# A-Main.net
KiCad netlist of a schematic drawn in Altium Designer
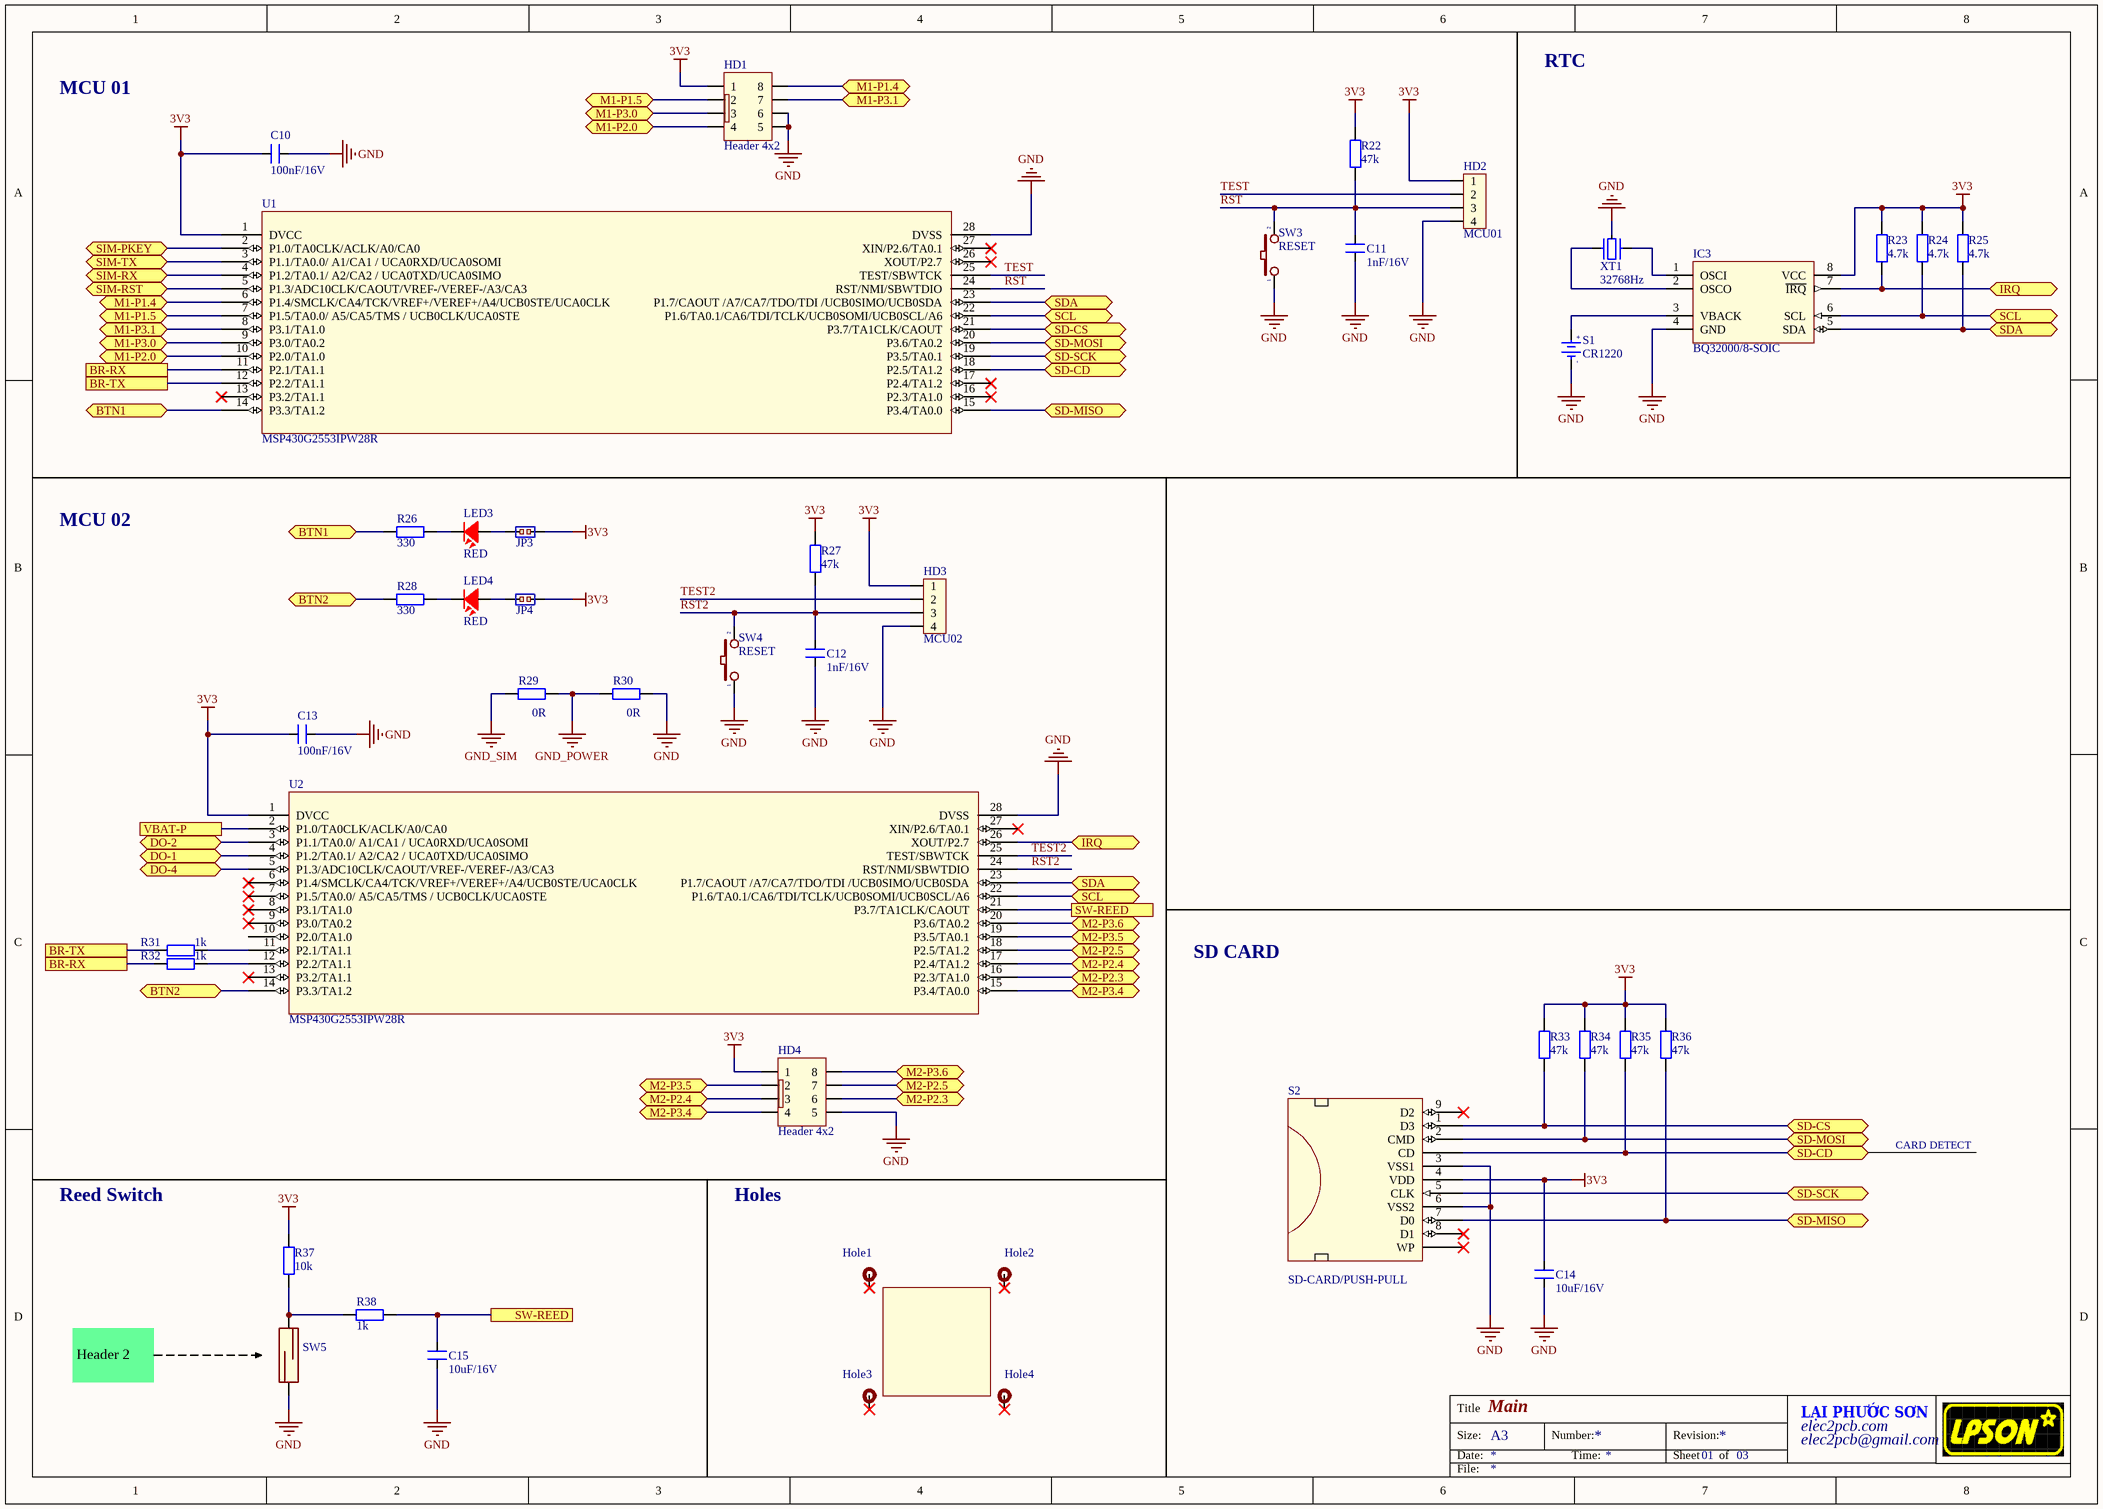
[diagram p0: A-Main.SchDoc]

(export (version "E")
  (design (tool "Eeschema 10.0.6"))
  (components
    (comp (ref "C10")
      (value "100nF/16V")
      (footprint "C0805-2012")
      (description "CAP CER 0.1UF 16V X7R 0805")
      (fields
        (field (name "MANUFACTURER") "Kemet")
        (field (name "MANUFACTURER PART NUMBER") "C0805C104K4RACTU")
      )
      (libsource (lib "Tran Tuan") (part "CAP-CER/100nF/16V/X7R/0805"))
    )
    (comp (ref "C11")
      (value "1nF/16V")
      (footprint "C0603-1608")
      (description "CAP CER 1000PF 16V X7R 0603")
      (fields
        (field (name "MANUFACTURER") "AVX Corporation")
        (field (name "MANUFACTURER PART NUMBER") "0603YC102KAT2A")
      )
      (libsource (lib "Tran Tuan") (part "CAP-CER/1nF/16V/X7R/0603"))
    )
    (comp (ref "C12")
      (value "1nF/16V")
      (footprint "C0603-1608")
      (description "CAP CER 1000PF 16V X7R 0603")
      (fields
        (field (name "MANUFACTURER") "AVX Corporation")
        (field (name "MANUFACTURER PART NUMBER") "0603YC102KAT2A")
      )
      (libsource (lib "Tran Tuan") (part "CAP-CER/1nF/16V/X7R/0603"))
    )
    (comp (ref "C13")
      (value "100nF/16V")
      (footprint "C0805-2012")
      (description "CAP CER 0.1UF 16V X7R 0805")
      (fields
        (field (name "MANUFACTURER") "Kemet")
        (field (name "MANUFACTURER PART NUMBER") "C0805C104K4RACTU")
      )
      (libsource (lib "Tran Tuan") (part "CAP-CER/100nF/16V/X7R/0805"))
    )
    (comp (ref "C14")
      (value "10uF/16V")
      (footprint "C0805-2012")
      (description "CAP CER 10UF 16V X5R 0805")
      (fields
        (field (name "MANUFACTURER") "Murata Electronics North America")
        (field (name "MANUFACTURER PART NUMBER") "GRM21BR61C106KE15L")
      )
      (libsource (lib "Tran Tuan") (part "CAP-CER/10UF/16V/X5R/0805"))
    )
    (comp (ref "C15")
      (value "10uF/16V")
      (footprint "C0805-2012")
      (description "CAP CER 10UF 16V X5R 0805")
      (fields
        (field (name "MANUFACTURER") "Murata Electronics North America")
        (field (name "MANUFACTURER PART NUMBER") "GRM21BR61C106KE15L")
      )
      (libsource (lib "Tran Tuan") (part "CAP-CER/10UF/16V/X5R/0805"))
    )
    (comp (ref "HD1")
      (value "Header 4x2")
      (footprint "HeaderSP_4x2")
      (description "HEADER, 4X2, 2.54MM, MALE")
      (libsource (lib "Tran Tuan") (part "HED-4X2/MALE/2.54MM-B"))
    )
    (comp (ref "HD2")
      (value "MCU01")
      (footprint "Header_4")
      (description "Header 4")
      (libsource (lib "Tran Tuan") (part "Hed4"))
    )
    (comp (ref "HD3")
      (value "MCU02")
      (footprint "Header_4")
      (description "Header 4")
      (libsource (lib "Tran Tuan") (part "Hed4"))
    )
    (comp (ref "HD4")
      (value "Header 4x2")
      (footprint "HeaderSP_4x2")
      (description "HEADER, 4X2, 2.54MM, MALE")
      (libsource (lib "Tran Tuan") (part "HED-4X2/MALE/2.54MM-B"))
    )
    (comp (ref "Hole1")
      (value "Pad Big")
      (footprint "Screw 3.0")
      (libsource (lib "Tran Tuan") (part "Pad_Big"))
    )
    (comp (ref "Hole2")
      (value "Pad Big")
      (footprint "Screw 3.0")
      (libsource (lib "Tran Tuan") (part "Pad_Big"))
    )
    (comp (ref "Hole3")
      (value "Pad Big")
      (footprint "Screw 3.0")
      (libsource (lib "Tran Tuan") (part "Pad_Big"))
    )
    (comp (ref "Hole4")
      (value "Pad Big")
      (footprint "Screw 3.0")
      (libsource (lib "Tran Tuan") (part "Pad_Big"))
    )
    (comp (ref "IC3")
      (value "BQ32000/8-SOIC")
      (footprint "RTC-BQ32000")
      (description "IC RTC CLK/CALENDAR I2C 8-SOIC")
      (fields
        (field (name "MANUFACTURER") "Texas Instruments")
        (field (name "MANUFACTURER PART NUMBER") "BQ32000DR")
      )
      (libsource (lib "Tran Tuan") (part "BQ32000/8-SOIC"))
    )
    (comp (ref "JP3")
      (value "JP2-ShortingJumper")
      (footprint "Header_2")
      (description "2.54mm 2-Pin Shorting Jumper")
      (libsource (lib "Tran Tuan") (part "JP2-ShortingJumper"))
    )
    (comp (ref "JP4")
      (value "JP2-ShortingJumper")
      (footprint "Header_2")
      (description "2.54mm 2-Pin Shorting Jumper")
      (libsource (lib "Tran Tuan") (part "JP2-ShortingJumper"))
    )
    (comp (ref "LED3")
      (value "RED")
      (footprint "Led 0805R")
      (description "LED RED CLEAR 0805 SMD")
      (fields
        (field (name "MANUFACTURER") "Lite-On Inc.")
        (field (name "MANUFACTURER PART NUMBER") "LTST-C171KRKT")
      )
      (libsource (lib "Tran Tuan") (part "LED-RED/CLEAR/0805"))
    )
    (comp (ref "LED4")
      (value "RED")
      (footprint "Led 0805R")
      (description "LED RED CLEAR 0805 SMD")
      (fields
        (field (name "MANUFACTURER") "Lite-On Inc.")
        (field (name "MANUFACTURER PART NUMBER") "LTST-C171KRKT")
      )
      (libsource (lib "Tran Tuan") (part "LED-RED/CLEAR/0805"))
    )
    (comp (ref "R22")
      (value "~")
      (footprint "RESC2012(0805)")
      (description "RES SMD 47K OHM 5% 1/8W 0805")
      (fields
        (field (name "MANUFACTURER") "Yageo")
        (field (name "MANUFACTURER PART NUMBER") "RC0805JR-0747KL")
        (field (name "RESISTANCE (OHMS)") "47k")
      )
      (libsource (lib "Tran Tuan") (part "RES-0805/±5%"))
    )
    (comp (ref "R23")
      (value "~")
      (footprint "RESC2012(0805)")
      (description "RES SMD 4.7K OHM 5% 1/8W 0805")
      (fields
        (field (name "MANUFACTURER") "Yageo")
        (field (name "MANUFACTURER PART NUMBER") "RC0805JR-074K7L")
        (field (name "RESISTANCE (OHMS)") "4.7k")
      )
      (libsource (lib "Tran Tuan") (part "RES-0805/±5%"))
    )
    (comp (ref "R24")
      (value "~")
      (footprint "RESC2012(0805)")
      (description "RES SMD 4.7K OHM 5% 1/8W 0805")
      (fields
        (field (name "MANUFACTURER") "Yageo")
        (field (name "MANUFACTURER PART NUMBER") "RC0805JR-074K7L")
        (field (name "RESISTANCE (OHMS)") "4.7k")
      )
      (libsource (lib "Tran Tuan") (part "RES-0805/±5%"))
    )
    (comp (ref "R25")
      (value "~")
      (footprint "RESC2012(0805)")
      (description "RES SMD 4.7K OHM 5% 1/8W 0805")
      (fields
        (field (name "MANUFACTURER") "Yageo")
        (field (name "MANUFACTURER PART NUMBER") "RC0805JR-074K7L")
        (field (name "RESISTANCE (OHMS)") "4.7k")
      )
      (libsource (lib "Tran Tuan") (part "RES-0805/±5%"))
    )
    (comp (ref "R26")
      (value "~")
      (footprint "RESC2012(0805)")
      (description "RES SMD 330 OHM 5% 1/8W 0805")
      (fields
        (field (name "MANUFACTURER") "Yageo")
        (field (name "MANUFACTURER PART NUMBER") "RC0805JR-07330RL")
        (field (name "RESISTANCE (OHMS)") "330")
      )
      (libsource (lib "") (part "RES-0805/±5%_1"))
    )
    (comp (ref "R27")
      (value "~")
      (footprint "RESC2012(0805)")
      (description "RES SMD 47K OHM 5% 1/8W 0805")
      (fields
        (field (name "MANUFACTURER") "Yageo")
        (field (name "MANUFACTURER PART NUMBER") "RC0805JR-0747KL")
        (field (name "RESISTANCE (OHMS)") "47k")
      )
      (libsource (lib "Tran Tuan") (part "RES-0805/±5%"))
    )
    (comp (ref "R28")
      (value "~")
      (footprint "RESC2012(0805)")
      (description "RES SMD 330 OHM 5% 1/8W 0805")
      (fields
        (field (name "MANUFACTURER") "Yageo")
        (field (name "MANUFACTURER PART NUMBER") "RC0805JR-07330RL")
        (field (name "RESISTANCE (OHMS)") "330")
      )
      (libsource (lib "") (part "RES-0805/±5%_1"))
    )
    (comp (ref "R29")
      (value "0R")
      (footprint "RESC2012(0805)")
      (description "RES SMD 330 OHM 5% 1/8W 0805")
      (fields
        (field (name "MANUFACTURER") "Yageo")
        (field (name "MANUFACTURER PART NUMBER") "RC0805JR-07330RL")
      )
      (libsource (lib "") (part "RES-0805/±5%_1"))
    )
    (comp (ref "R30")
      (value "0R")
      (footprint "RESC2012(0805)")
      (description "RES SMD 330 OHM 5% 1/8W 0805")
      (fields
        (field (name "MANUFACTURER") "Yageo")
        (field (name "MANUFACTURER PART NUMBER") "RC0805JR-07330RL")
      )
      (libsource (lib "") (part "RES-0805/±5%_1"))
    )
    (comp (ref "R31")
      (value "~")
      (footprint "RESC2012(0805)")
      (description "RES SMD 1K OHM 5% 1/8W 0805")
      (fields
        (field (name "MANUFACTURER") "Yageo")
        (field (name "MANUFACTURER PART NUMBER") "RC0805JR-071KL")
        (field (name "RESISTANCE (OHMS)") "1k")
      )
      (libsource (lib "") (part "RES-0805/±5%_1"))
    )
    (comp (ref "R32")
      (value "~")
      (footprint "RESC2012(0805)")
      (description "RES SMD 1K OHM 5% 1/8W 0805")
      (fields
        (field (name "MANUFACTURER") "Yageo")
        (field (name "MANUFACTURER PART NUMBER") "RC0805JR-071KL")
        (field (name "RESISTANCE (OHMS)") "1k")
      )
      (libsource (lib "") (part "RES-0805/±5%_1"))
    )
    (comp (ref "R33")
      (value "~")
      (footprint "RESC2012(0805)")
      (description "RES SMD 47K OHM 5% 1/8W 0805")
      (fields
        (field (name "MANUFACTURER") "Yageo")
        (field (name "MANUFACTURER PART NUMBER") "RC0805JR-0747KL")
        (field (name "RESISTANCE (OHMS)") "47k")
      )
      (libsource (lib "Tran Tuan") (part "RES-0805/±5%"))
    )
    (comp (ref "R34")
      (value "~")
      (footprint "RESC2012(0805)")
      (description "RES SMD 47K OHM 5% 1/8W 0805")
      (fields
        (field (name "MANUFACTURER") "Yageo")
        (field (name "MANUFACTURER PART NUMBER") "RC0805JR-0747KL")
        (field (name "RESISTANCE (OHMS)") "47k")
      )
      (libsource (lib "Tran Tuan") (part "RES-0805/±5%"))
    )
    (comp (ref "R35")
      (value "~")
      (footprint "RESC2012(0805)")
      (description "RES SMD 47K OHM 5% 1/8W 0805")
      (fields
        (field (name "MANUFACTURER") "Yageo")
        (field (name "MANUFACTURER PART NUMBER") "RC0805JR-0747KL")
        (field (name "RESISTANCE (OHMS)") "47k")
      )
      (libsource (lib "Tran Tuan") (part "RES-0805/±5%"))
    )
    (comp (ref "R36")
      (value "~")
      (footprint "RESC2012(0805)")
      (description "RES SMD 47K OHM 5% 1/8W 0805")
      (fields
        (field (name "MANUFACTURER") "Yageo")
        (field (name "MANUFACTURER PART NUMBER") "RC0805JR-0747KL")
        (field (name "RESISTANCE (OHMS)") "47k")
      )
      (libsource (lib "Tran Tuan") (part "RES-0805/±5%"))
    )
    (comp (ref "R37")
      (value "~")
      (footprint "RESC2012(0805)")
      (description "RES SMD 10K OHM 5% 1/8W 0805")
      (fields
        (field (name "MANUFACTURER") "Yageo")
        (field (name "MANUFACTURER PART NUMBER") "RC0805JR-0710KL")
        (field (name "RESISTANCE (OHMS)") "10k")
      )
      (libsource (lib "") (part "RES-0805/±5%_2"))
    )
    (comp (ref "R38")
      (value "~")
      (footprint "RESC2012(0805)")
      (description "RES SMD 1K OHM 5% 1/8W 0805")
      (fields
        (field (name "MANUFACTURER") "Yageo")
        (field (name "MANUFACTURER PART NUMBER") "RC0805JR-071KL")
        (field (name "RESISTANCE (OHMS)") "1k")
      )
      (libsource (lib "") (part "RES-0805/±5%_1"))
    )
    (comp (ref "S1")
      (value "CR1220")
      (footprint "Socket-PIN-BC501SM-TR")
      (description "CR1220 Battery Holder SMD")
      (fields (field (name "Comment") "BAT-HOLDER/CR1220/TME"))
      (libsource (lib "Tran Tuan") (part "BAT-HOLDER/CR1220/TME"))
    )
    (comp (ref "S2")
      (value "SD-CARD/PUSH-PULL")
      (footprint "SD-CARD")
      (description "CONN SD CARD PUSH-PUSH R/A SMD")
      (fields
        (field (name "MANUFACTURER") "Amphenol Commercial Products")
        (field (name "MANUFACTURER PART NUMBER") "101-00313-68-02")
      )
      (libsource (lib "Tran Tuan") (part "SD-CARD/PUSH-PULL"))
    )
    (comp (ref "SW3")
      (value "RESET")
      (footprint "BTN-EVQ-11A04M")
      (description "SWITCH TACTILE SPST-NO 0.02A 15V")
      (fields
        (field (name "MANUFACTURER") "Panasonic Electronic Components")
        (field (name "MANUFACTURER PART NUMBER") "EVQ-11A04M")
      )
      (libsource (lib "Tran Tuan") (part "SW2-PUSH/SPST/NO"))
    )
    (comp (ref "SW4")
      (value "RESET")
      (footprint "BTN-EVQ-11A04M")
      (description "SWITCH TACTILE SPST-NO 0.02A 15V")
      (fields
        (field (name "MANUFACTURER") "Panasonic Electronic Components")
        (field (name "MANUFACTURER PART NUMBER") "EVQ-11A04M")
      )
      (libsource (lib "Tran Tuan") (part "SW2-PUSH/SPST/NO"))
    )
    (comp (ref "SW5")
      (value "SW-REED/SPST/NO/350mA")
      (footprint "SWITCH-SDSM")
      (description "SWITCH REED SPST-NO 350MA 140V")
      (fields
        (field (name "MANUFACTURER") "Littelfuse Inc.")
        (field (name "MANUFACTURER PART NUMBER") "MDSM-4R-12-18")
      )
      (libsource (lib "Tran Tuan") (part "SW-REED/SPST/NO/350mA"))
    )
    (comp (ref "U1")
      (value "MSP430G2553IPW28R")
      (footprint "MSP430G2253IPW28R")
      (description "IC MCU 16BIT 16KB FLASH 28TSSOP")
      (fields (field (name "MANUFACTURER") "Texas Instruments"))
      (libsource (lib "Tran Tuan") (part "MSP430G2553IPW28R"))
    )
    (comp (ref "U2")
      (value "MSP430G2553IPW28R")
      (footprint "MSP430G2253IPW28R")
      (description "IC MCU 16BIT 16KB FLASH 28TSSOP")
      (fields (field (name "MANUFACTURER") "Texas Instruments"))
      (libsource (lib "Tran Tuan") (part "MSP430G2553IPW28R"))
    )
    (comp (ref "XT1")
      (value "32768Hz")
      (footprint "CR_32768")
      (description "CRYSTAL 32.7680KHZ 12.5PF T/H")
      (fields
        (field (name "MANUFACTURER") "Citizen Finedevice Co Ltd")
        (field (name "MANUFACTURER PART NUMBER") "CFS206-32.768KDZF-UB")
      )
      (libsource (lib "Tran Tuan") (part "XT-32768HZ/RADIAL"))
    )
  )
  (nets
    (net (code "1") (name "/BR-RX") (class "Default")
      (node (ref "R32") (pin "2") (pinfunction "2_2") (pintype "passive"))
      (node (ref "U1") (pin "11") (pinfunction "P2.1/TA1.1_11") (pintype "bidirectional"))
    )
    (net (code "2") (name "/BR-TX") (class "Default")
      (node (ref "R31") (pin "2") (pinfunction "2_2") (pintype "passive"))
      (node (ref "U1") (pin "12") (pinfunction "P2.2/TA1.1_12") (pintype "bidirectional"))
    )
    (net (code "3") (name "/BTN1") (class "Default")
      (node (ref "R26") (pin "2") (pinfunction "2_2") (pintype "passive"))
      (node (ref "U1") (pin "14") (pinfunction "P3.3/TA1.2_14") (pintype "bidirectional"))
    )
    (net (code "4") (name "/BTN2") (class "Default")
      (node (ref "R28") (pin "2") (pinfunction "2_2") (pintype "passive"))
      (node (ref "U2") (pin "14") (pinfunction "P3.3/TA1.2_14") (pintype "bidirectional"))
    )
    (net (code "5") (name "/DO-1") (class "Default")
      (node (ref "U2") (pin "4") (pinfunction "P1.2/TA0.1/_A2/CA2_/_UCA0TXD/UCA0SIMO_4") (pintype "bidirectional"))
    )
    (net (code "6") (name "/DO-2") (class "Default")
      (node (ref "U2") (pin "3") (pinfunction "P1.1/TA0.0/_A1/CA1_/_UCA0RXD/UCA0SOMI_3") (pintype "bidirectional"))
    )
    (net (code "7") (name "/DO-4") (class "Default")
      (node (ref "U2") (pin "5") (pinfunction "P1.3/ADC10CLK/CAOUT/VREF-/VEREF-/A3/CA3_5") (pintype "bidirectional"))
    )
    (net (code "8") (name "/IRQ") (class "Default")
      (node (ref "IC3") (pin "7") (pinfunction "~{IRQ}_7") (pintype "output"))
      (node (ref "R23") (pin "1") (pinfunction "1_1") (pintype "passive"))
      (node (ref "U2") (pin "26") (pinfunction "XOUT/P2.7_26") (pintype "bidirectional"))
    )
    (net (code "9") (name "/M1-P1.4") (class "Default")
      (node (ref "HD1") (pin "8") (pinfunction "8_8") (pintype "passive"))
      (node (ref "U1") (pin "6") (pinfunction "P1.4/SMCLK/CA4/TCK/VREF+/VEREF+/A4/UCB0STE/UCA0CLK_6") (pintype "bidirectional"))
    )
    (net (code "10") (name "/M1-P1.5") (class "Default")
      (node (ref "HD1") (pin "2") (pinfunction "2_2") (pintype "passive"))
      (node (ref "U1") (pin "7") (pinfunction "P1.5/TA0.0/_A5/CA5/TMS_/_UCB0CLK/UCA0STE_7") (pintype "bidirectional"))
    )
    (net (code "11") (name "/M1-P2.0") (class "Default")
      (node (ref "HD1") (pin "4") (pinfunction "4_4") (pintype "passive"))
      (node (ref "U1") (pin "10") (pinfunction "P2.0/TA1.0_10") (pintype "bidirectional"))
    )
    (net (code "12") (name "/M1-P3.0") (class "Default")
      (node (ref "HD1") (pin "3") (pinfunction "3_3") (pintype "passive"))
      (node (ref "U1") (pin "9") (pinfunction "P3.0/TA0.2_9") (pintype "bidirectional"))
    )
    (net (code "13") (name "/M1-P3.1") (class "Default")
      (node (ref "HD1") (pin "7") (pinfunction "7_7") (pintype "passive"))
      (node (ref "U1") (pin "8") (pinfunction "P3.1/TA1.0_8") (pintype "bidirectional"))
    )
    (net (code "14") (name "/M2-P2.3") (class "Default")
      (node (ref "HD4") (pin "6") (pinfunction "6_6") (pintype "passive"))
      (node (ref "U2") (pin "16") (pinfunction "P2.3/TA1.0_16") (pintype "bidirectional"))
    )
    (net (code "15") (name "/M2-P2.4") (class "Default")
      (node (ref "HD4") (pin "3") (pinfunction "3_3") (pintype "passive"))
      (node (ref "U2") (pin "17") (pinfunction "P2.4/TA1.2_17") (pintype "bidirectional"))
    )
    (net (code "16") (name "/M2-P2.5") (class "Default")
      (node (ref "HD4") (pin "7") (pinfunction "7_7") (pintype "passive"))
      (node (ref "U2") (pin "18") (pinfunction "P2.5/TA1.2_18") (pintype "bidirectional"))
    )
    (net (code "17") (name "/M2-P3.4") (class "Default")
      (node (ref "HD4") (pin "4") (pinfunction "4_4") (pintype "passive"))
      (node (ref "U2") (pin "15") (pinfunction "P3.4/TA0.0_15") (pintype "bidirectional"))
    )
    (net (code "18") (name "/M2-P3.5") (class "Default")
      (node (ref "HD4") (pin "2") (pinfunction "2_2") (pintype "passive"))
      (node (ref "U2") (pin "19") (pinfunction "P3.5/TA0.1_19") (pintype "bidirectional"))
    )
    (net (code "19") (name "/M2-P3.6") (class "Default")
      (node (ref "HD4") (pin "8") (pinfunction "8_8") (pintype "passive"))
      (node (ref "U2") (pin "20") (pinfunction "P3.6/TA0.2_20") (pintype "bidirectional"))
    )
    (net (code "20") (name "/RST") (class "Default")
      (node (ref "C11") (pin "1") (pinfunction "1_1") (pintype "passive"))
      (node (ref "HD2") (pin "3") (pinfunction "3_3") (pintype "passive"))
      (node (ref "R22") (pin "1") (pinfunction "1_1") (pintype "passive"))
      (node (ref "SW3") (pin "2") (pinfunction "2_2") (pintype "passive"))
      (node (ref "U1") (pin "24") (pinfunction "RST/NMI/SBWTDIO_24") (pintype "passive"))
    )
    (net (code "21") (name "/RST2") (class "Default")
      (node (ref "C12") (pin "1") (pinfunction "1_1") (pintype "passive"))
      (node (ref "HD3") (pin "3") (pinfunction "3_3") (pintype "passive"))
      (node (ref "R27") (pin "1") (pinfunction "1_1") (pintype "passive"))
      (node (ref "SW4") (pin "2") (pinfunction "2_2") (pintype "passive"))
      (node (ref "U2") (pin "24") (pinfunction "RST/NMI/SBWTDIO_24") (pintype "passive"))
    )
    (net (code "22") (name "/SCL") (class "Default")
      (node (ref "IC3") (pin "6") (pinfunction "SCL_6") (pintype "input"))
      (node (ref "R24") (pin "1") (pinfunction "1_1") (pintype "passive"))
      (node (ref "U1") (pin "22") (pinfunction "P1.6/TA0.1/CA6/TDI/TCLK/UCB0SOMI/UCB0SCL/A6_22") (pintype "bidirectional"))
      (node (ref "U2") (pin "22") (pinfunction "P1.6/TA0.1/CA6/TDI/TCLK/UCB0SOMI/UCB0SCL/A6_22") (pintype "bidirectional"))
    )
    (net (code "23") (name "/SD-CD") (class "Default")
      (node (ref "R35") (pin "1") (pinfunction "1_1") (pintype "passive"))
      (node (ref "S2") (pin "CD") (pinfunction "CD_CD") (pintype "passive"))
      (node (ref "U1") (pin "18") (pinfunction "P2.5/TA1.2_18") (pintype "bidirectional"))
    )
    (net (code "24") (name "/SD-CS") (class "Default")
      (node (ref "R33") (pin "1") (pinfunction "1_1") (pintype "passive"))
      (node (ref "S2") (pin "1") (pinfunction "D3_1") (pintype "bidirectional"))
      (node (ref "U1") (pin "21") (pinfunction "P3.7/TA1CLK/CAOUT_21") (pintype "bidirectional"))
    )
    (net (code "25") (name "/SD-MISO") (class "Default")
      (node (ref "R36") (pin "1") (pinfunction "1_1") (pintype "passive"))
      (node (ref "S2") (pin "7") (pinfunction "D0_7") (pintype "bidirectional"))
      (node (ref "U1") (pin "15") (pinfunction "P3.4/TA0.0_15") (pintype "bidirectional"))
    )
    (net (code "26") (name "/SD-MOSI") (class "Default")
      (node (ref "R34") (pin "1") (pinfunction "1_1") (pintype "passive"))
      (node (ref "S2") (pin "2") (pinfunction "CMD_2") (pintype "bidirectional"))
      (node (ref "U1") (pin "20") (pinfunction "P3.6/TA0.2_20") (pintype "bidirectional"))
    )
    (net (code "27") (name "/SD-SCK") (class "Default")
      (node (ref "S2") (pin "5") (pinfunction "CLK_5") (pintype "input"))
      (node (ref "U1") (pin "19") (pinfunction "P3.5/TA0.1_19") (pintype "bidirectional"))
    )
    (net (code "28") (name "/SDA") (class "Default")
      (node (ref "IC3") (pin "5") (pinfunction "SDA_5") (pintype "bidirectional"))
      (node (ref "R25") (pin "1") (pinfunction "1_1") (pintype "passive"))
      (node (ref "U1") (pin "23") (pinfunction "P1.7/CAOUT_/A7/CA7/TDO/TDI_/UCB0SIMO/UCB0SDA_23") (pintype "bidirectional"))
      (node (ref "U2") (pin "23") (pinfunction "P1.7/CAOUT_/A7/CA7/TDO/TDI_/UCB0SIMO/UCB0SDA_23") (pintype "bidirectional"))
    )
    (net (code "29") (name "/SIM-PKEY") (class "Default")
      (node (ref "U1") (pin "2") (pinfunction "P1.0/TA0CLK/ACLK/A0/CA0_2") (pintype "bidirectional"))
    )
    (net (code "30") (name "/SIM-RST") (class "Default")
      (node (ref "U1") (pin "5") (pinfunction "P1.3/ADC10CLK/CAOUT/VREF-/VEREF-/A3/CA3_5") (pintype "bidirectional"))
    )
    (net (code "31") (name "/SIM-RX") (class "Default")
      (node (ref "U1") (pin "4") (pinfunction "P1.2/TA0.1/_A2/CA2_/_UCA0TXD/UCA0SIMO_4") (pintype "bidirectional"))
    )
    (net (code "32") (name "/SIM-TX") (class "Default")
      (node (ref "U1") (pin "3") (pinfunction "P1.1/TA0.0/_A1/CA1_/_UCA0RXD/UCA0SOMI_3") (pintype "bidirectional"))
    )
    (net (code "33") (name "/SW-REED") (class "Default")
      (node (ref "C15") (pin "1") (pinfunction "1_1") (pintype "passive"))
      (node (ref "R38") (pin "1") (pinfunction "1_1") (pintype "passive"))
      (node (ref "U2") (pin "21") (pinfunction "P3.7/TA1CLK/CAOUT_21") (pintype "bidirectional"))
    )
    (net (code "34") (name "/TEST") (class "Default")
      (node (ref "HD2") (pin "2") (pinfunction "2_2") (pintype "passive"))
      (node (ref "U1") (pin "25") (pinfunction "TEST/SBWTCK_25") (pintype "passive"))
    )
    (net (code "35") (name "/TEST2") (class "Default")
      (node (ref "HD3") (pin "2") (pinfunction "2_2") (pintype "passive"))
      (node (ref "U2") (pin "25") (pinfunction "TEST/SBWTCK_25") (pintype "passive"))
    )
    (net (code "36") (name "/VBAT-P") (class "Default")
      (node (ref "U2") (pin "2") (pinfunction "P1.0/TA0CLK/ACLK/A0/CA0_2") (pintype "bidirectional"))
    )
    (net (code "37") (name "3V3") (class "Default")
      (node (ref "C10") (pin "1") (pinfunction "1_1") (pintype "passive"))
      (node (ref "C13") (pin "1") (pinfunction "1_1") (pintype "passive"))
      (node (ref "C14") (pin "1") (pinfunction "1_1") (pintype "passive"))
      (node (ref "HD1") (pin "1") (pinfunction "1_1") (pintype "passive"))
      (node (ref "HD2") (pin "1") (pinfunction "1_1") (pintype "passive"))
      (node (ref "HD3") (pin "1") (pinfunction "1_1") (pintype "passive"))
      (node (ref "HD4") (pin "1") (pinfunction "1_1") (pintype "passive"))
      (node (ref "IC3") (pin "8") (pinfunction "VCC_8") (pintype "power_in"))
      (node (ref "JP3") (pin "2") (pinfunction "2_2") (pintype "passive"))
      (node (ref "JP4") (pin "2") (pinfunction "2_2") (pintype "passive"))
      (node (ref "R22") (pin "2") (pinfunction "2_2") (pintype "passive"))
      (node (ref "R23") (pin "2") (pinfunction "2_2") (pintype "passive"))
      (node (ref "R24") (pin "2") (pinfunction "2_2") (pintype "passive"))
      (node (ref "R25") (pin "2") (pinfunction "2_2") (pintype "passive"))
      (node (ref "R27") (pin "2") (pinfunction "2_2") (pintype "passive"))
      (node (ref "R33") (pin "2") (pinfunction "2_2") (pintype "passive"))
      (node (ref "R34") (pin "2") (pinfunction "2_2") (pintype "passive"))
      (node (ref "R35") (pin "2") (pinfunction "2_2") (pintype "passive"))
      (node (ref "R36") (pin "2") (pinfunction "2_2") (pintype "passive"))
      (node (ref "R37") (pin "1") (pinfunction "1_1") (pintype "passive"))
      (node (ref "S2") (pin "4") (pinfunction "VDD_4") (pintype "power_in"))
      (node (ref "U1") (pin "1") (pinfunction "DVCC_1") (pintype "power_in"))
      (node (ref "U2") (pin "1") (pinfunction "DVCC_1") (pintype "power_in"))
    )
    (net (code "38") (name "GND") (class "Default")
      (node (ref "C10") (pin "2") (pinfunction "2_2") (pintype "passive"))
      (node (ref "C11") (pin "2") (pinfunction "2_2") (pintype "passive"))
      (node (ref "C12") (pin "2") (pinfunction "2_2") (pintype "passive"))
      (node (ref "C13") (pin "2") (pinfunction "2_2") (pintype "passive"))
      (node (ref "C14") (pin "2") (pinfunction "2_2") (pintype "passive"))
      (node (ref "C15") (pin "2") (pinfunction "2_2") (pintype "passive"))
      (node (ref "HD1") (pin "5") (pinfunction "5_5") (pintype "passive"))
      (node (ref "HD1") (pin "6") (pinfunction "6_6") (pintype "passive"))
      (node (ref "HD2") (pin "4") (pinfunction "4_4") (pintype "passive"))
      (node (ref "HD3") (pin "4") (pinfunction "4_4") (pintype "passive"))
      (node (ref "HD4") (pin "5") (pinfunction "5_5") (pintype "passive"))
      (node (ref "IC3") (pin "4") (pinfunction "GND_4") (pintype "power_in"))
      (node (ref "R30") (pin "1") (pinfunction "1_1") (pintype "passive"))
      (node (ref "S1") (pin "2") (pinfunction "GND_2") (pintype "passive"))
      (node (ref "S2") (pin "3") (pinfunction "VSS1_3") (pintype "power_in"))
      (node (ref "S2") (pin "6") (pinfunction "VSS2_6") (pintype "power_in"))
      (node (ref "SW3") (pin "1") (pinfunction "1_1") (pintype "passive"))
      (node (ref "SW4") (pin "1") (pinfunction "1_1") (pintype "passive"))
      (node (ref "SW5") (pin "1") (pinfunction "1_1") (pintype "passive"))
      (node (ref "U1") (pin "28") (pinfunction "DVSS_28") (pintype "passive"))
      (node (ref "U2") (pin "28") (pinfunction "DVSS_28") (pintype "passive"))
      (node (ref "XT1") (pin "0") (pinfunction "Case_0") (pintype "passive"))
    )
    (net (code "39") (name "GND_POWER") (class "Default")
      (node (ref "R29") (pin "1") (pinfunction "1_1") (pintype "passive"))
      (node (ref "R30") (pin "2") (pinfunction "2_2") (pintype "passive"))
    )
    (net (code "40") (name "GND_SIM") (class "Default")
      (node (ref "R29") (pin "2") (pinfunction "2_2") (pintype "passive"))
    )
    (net (code "41") (name "Net-(IC3-OSCI)") (class "Default")
      (node (ref "IC3") (pin "1") (pinfunction "OSCI_1") (pintype "passive"))
      (node (ref "XT1") (pin "2") (pinfunction "2_2") (pintype "passive"))
    )
    (net (code "42") (name "Net-(IC3-OSCO)") (class "Default")
      (node (ref "IC3") (pin "2") (pinfunction "OSCO_2") (pintype "passive"))
      (node (ref "XT1") (pin "1") (pinfunction "1_1") (pintype "passive"))
    )
    (net (code "43") (name "Net-(IC3-VBACK)") (class "Default")
      (node (ref "IC3") (pin "3") (pinfunction "VBACK_3") (pintype "power_in"))
      (node (ref "S1") (pin "1") (pinfunction "+3V_1") (pintype "passive"))
    )
    (net (code "44") (name "Net-(LED3-A)") (class "Default")
      (node (ref "JP3") (pin "1") (pinfunction "1_1") (pintype "passive"))
      (node (ref "LED3") (pin "1") (pinfunction "A_1") (pintype "passive"))
    )
    (net (code "45") (name "Net-(LED3-K)") (class "Default")
      (node (ref "LED3") (pin "2") (pinfunction "K_2") (pintype "passive"))
      (node (ref "R26") (pin "1") (pinfunction "1_1") (pintype "passive"))
    )
    (net (code "46") (name "Net-(LED4-A)") (class "Default")
      (node (ref "JP4") (pin "1") (pinfunction "1_1") (pintype "passive"))
      (node (ref "LED4") (pin "1") (pinfunction "A_1") (pintype "passive"))
    )
    (net (code "47") (name "Net-(LED4-K)") (class "Default")
      (node (ref "LED4") (pin "2") (pinfunction "K_2") (pintype "passive"))
      (node (ref "R28") (pin "1") (pinfunction "1_1") (pintype "passive"))
    )
    (net (code "48") (name "Net-(R37-Pad2)") (class "Default")
      (node (ref "R37") (pin "2") (pinfunction "2_2") (pintype "passive"))
      (node (ref "R38") (pin "2") (pinfunction "2_2") (pintype "passive"))
      (node (ref "SW5") (pin "2") (pinfunction "2_2") (pintype "passive"))
    )
    (net (code "49") (name "Net-(U2-P2.1{slash}TA1.1)") (class "Default")
      (node (ref "R31") (pin "1") (pinfunction "1_1") (pintype "passive"))
      (node (ref "U2") (pin "11") (pinfunction "P2.1/TA1.1_11") (pintype "bidirectional"))
    )
    (net (code "50") (name "Net-(U2-P2.2{slash}TA1.1)") (class "Default")
      (node (ref "R32") (pin "1") (pinfunction "1_1") (pintype "passive"))
      (node (ref "U2") (pin "12") (pinfunction "P2.2/TA1.1_12") (pintype "bidirectional"))
    )
    (net (code "51") (name "unconnected-(Hole1-Pad1)") (class "Default")
      (node (ref "Hole1") (pin "1") (pinfunction "1_1") (pintype "passive+no_connect"))
    )
    (net (code "52") (name "unconnected-(Hole2-Pad1)") (class "Default")
      (node (ref "Hole2") (pin "1") (pinfunction "1_1") (pintype "passive+no_connect"))
    )
    (net (code "53") (name "unconnected-(Hole3-Pad1)") (class "Default")
      (node (ref "Hole3") (pin "1") (pinfunction "1_1") (pintype "passive+no_connect"))
    )
    (net (code "54") (name "unconnected-(Hole4-Pad1)") (class "Default")
      (node (ref "Hole4") (pin "1") (pinfunction "1_1") (pintype "passive+no_connect"))
    )
    (net (code "55") (name "unconnected-(S2-D1-Pad8)") (class "Default")
      (node (ref "S2") (pin "8") (pinfunction "D1_8") (pintype "bidirectional+no_connect"))
    )
    (net (code "56") (name "unconnected-(S2-D2-Pad9)") (class "Default")
      (node (ref "S2") (pin "9") (pinfunction "D2_9") (pintype "bidirectional+no_connect"))
    )
    (net (code "57") (name "unconnected-(S2-PadWP)") (class "Default")
      (node (ref "S2") (pin "WP") (pinfunction "WP_WP") (pintype "passive+no_connect"))
    )
    (net (code "58") (name "unconnected-(U1-P2.3{slash}TA1.0-Pad16)") (class "Default")
      (node (ref "U1") (pin "16") (pinfunction "P2.3/TA1.0_16") (pintype "bidirectional+no_connect"))
    )
    (net (code "59") (name "unconnected-(U1-P2.4{slash}TA1.2-Pad17)") (class "Default")
      (node (ref "U1") (pin "17") (pinfunction "P2.4/TA1.2_17") (pintype "bidirectional+no_connect"))
    )
    (net (code "60") (name "unconnected-(U1-P3.2{slash}TA1.1-Pad13)") (class "Default")
      (node (ref "U1") (pin "13") (pinfunction "P3.2/TA1.1_13") (pintype "bidirectional+no_connect"))
    )
    (net (code "61") (name "unconnected-(U1-XIN{slash}P2.6{slash}TA0.1-Pad27)") (class "Default")
      (node (ref "U1") (pin "27") (pinfunction "XIN/P2.6/TA0.1_27") (pintype "bidirectional+no_connect"))
    )
    (net (code "62") (name "unconnected-(U1-XOUT{slash}P2.7-Pad26)") (class "Default")
      (node (ref "U1") (pin "26") (pinfunction "XOUT/P2.7_26") (pintype "bidirectional+no_connect"))
    )
    (net (code "63") (name "unconnected-(U2-P1.4{slash}SMCLK{slash}CA4{slash}TCK{slash}VREF+{slash}VEREF+{slash}A4{slash}UCB0STE{slash}UCA0CLK-Pad6)") (class "Default")
      (node (ref "U2") (pin "6") (pinfunction "P1.4/SMCLK/CA4/TCK/VREF+/VEREF+/A4/UCB0STE/UCA0CLK_6") (pintype "bidirectional+no_connect"))
    )
    (net (code "64") (name "unconnected-(U2-P1.5{slash}TA0.0{slash}_A5{slash}CA5{slash}TMS_{slash}_UCB0CLK{slash}UCA0STE-Pad7)") (class "Default")
      (node (ref "U2") (pin "7") (pinfunction "P1.5/TA0.0/_A5/CA5/TMS_/_UCB0CLK/UCA0STE_7") (pintype "bidirectional+no_connect"))
    )
    (net (code "65") (name "unconnected-(U2-P2.0{slash}TA1.0-Pad10)") (class "Default")
      (node (ref "U2") (pin "10") (pinfunction "P2.0/TA1.0_10") (pintype "bidirectional"))
    )
    (net (code "66") (name "unconnected-(U2-P3.0{slash}TA0.2-Pad9)") (class "Default")
      (node (ref "U2") (pin "9") (pinfunction "P3.0/TA0.2_9") (pintype "bidirectional+no_connect"))
    )
    (net (code "67") (name "unconnected-(U2-P3.1{slash}TA1.0-Pad8)") (class "Default")
      (node (ref "U2") (pin "8") (pinfunction "P3.1/TA1.0_8") (pintype "bidirectional+no_connect"))
    )
    (net (code "68") (name "unconnected-(U2-P3.2{slash}TA1.1-Pad13)") (class "Default")
      (node (ref "U2") (pin "13") (pinfunction "P3.2/TA1.1_13") (pintype "bidirectional+no_connect"))
    )
    (net (code "69") (name "unconnected-(U2-XIN{slash}P2.6{slash}TA0.1-Pad27)") (class "Default")
      (node (ref "U2") (pin "27") (pinfunction "XIN/P2.6/TA0.1_27") (pintype "bidirectional+no_connect"))
    )
  )
)
